# Sensors.net
KiCad netlist of a schematic drawn in Altium Designer
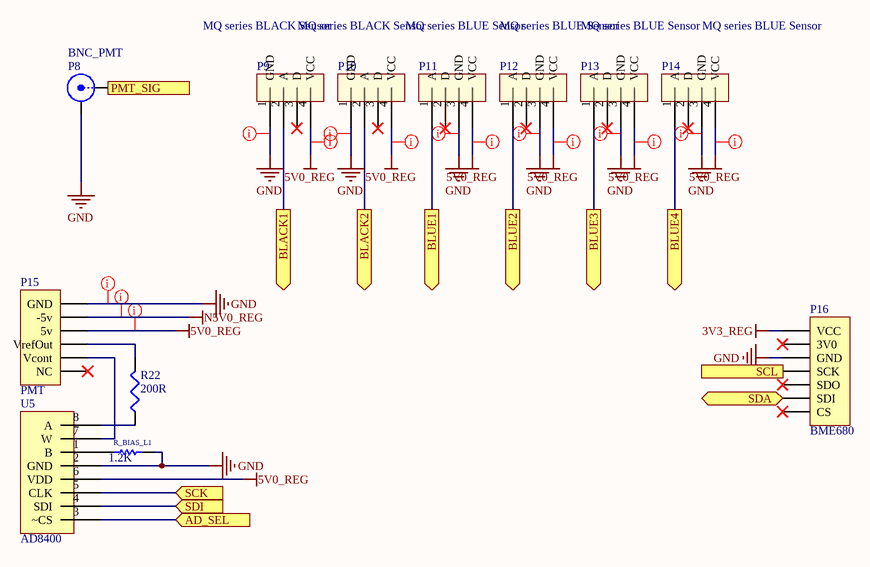
[diagram p0: Sensors.SchDoc]

(export (version "E")
  (design (tool "Eeschema 10.0.6"))
  (components
    (comp (ref "P8")
      (value "BNC_PMT")
      (footprint "BNC_RA CON")
      (description "BNC Elbow Connector")
      (fields (field (name "PUBLISHER") "Altium Limited"))
      (libsource (lib "Miscellaneous Connectors") (part "BNC"))
    )
    (comp (ref "P9")
      (value "MQ series BLACK Sensor")
      (footprint "MQ series BLACK sensor")
      (libsource (lib "ScienceComponents") (part "MQ series BLACK Sensor"))
    )
    (comp (ref "P10")
      (value "MQ series BLACK Sensor")
      (footprint "MQ series BLACK sensor")
      (libsource (lib "ScienceComponents") (part "MQ series BLACK Sensor"))
    )
    (comp (ref "P11")
      (value "MQ series BLUE Sensor")
      (footprint "MQ series BLUE sensor")
      (libsource (lib "ScienceComponents") (part "MQ series BLUE Sensor"))
    )
    (comp (ref "P12")
      (value "MQ series BLUE Sensor")
      (footprint "MQ series BLUE sensor")
      (libsource (lib "ScienceComponents") (part "MQ series BLUE Sensor"))
    )
    (comp (ref "P13")
      (value "MQ series BLUE Sensor")
      (footprint "MQ series BLUE sensor")
      (libsource (lib "ScienceComponents") (part "MQ series BLUE Sensor"))
    )
    (comp (ref "P14")
      (value "MQ series BLUE Sensor")
      (footprint "MQ series BLUE sensor")
      (libsource (lib "ScienceComponents") (part "MQ series BLUE Sensor"))
    )
    (comp (ref "P15")
      (value "PMT")
      (footprint "HDR1X6H")
      (description "Header, 6-Pin, Right Angle")
      (fields (field (name "PUBLISHER") "Altium Limited"))
      (libsource (lib "Miscellaneous Connectors") (part "Header 6H"))
    )
    (comp (ref "P16")
      (value "BME680")
      (footprint "HDR1X7")
      (description "Header, 7-Pin")
      (fields (field (name "PUBLISHER") "Altium Limited"))
      (libsource (lib "Miscellaneous Connectors") (part "Header 7"))
    )
    (comp (ref "R22")
      (value "200R")
      (footprint "RESC1608X06N_0603")
      (description "RES SMD 200 OHM 1% 1/4W 1206")
      (fields (field (name "TOLERANCE") "1%"))
      (libsource (lib "RSX_Resistors") (part "RC1206FR-07200RL"))
    )
    (comp (ref "R_BIAS_L1")
      (value "1.2K")
      (footprint "RESC1608X06N_0603")
      (description "Resistor")
      (fields (field (name "PUBLISHER") "Altium Limited"))
      (libsource (lib "Miscellaneous Devices") (part "Res1"))
    )
    (comp (ref "U5")
      (value "AD8400")
      (footprint "AD8400(SOIC8)")
      (libsource (lib "DUE") (part "Component_1"))
    )
  )
  (nets
    (net (code "1") (name "/AD_SEL") (class "Default")
      (node (ref "U5") (pin "3") (pinfunction "~CS_3") (pintype "passive"))
    )
    (net (code "2") (name "/BLACK1") (class "Default")
      (node (ref "P9") (pin "2") (pinfunction "A_2") (pintype "passive"))
    )
    (net (code "3") (name "/BLACK2") (class "Default")
      (node (ref "P10") (pin "2") (pinfunction "A_2") (pintype "passive"))
    )
    (net (code "4") (name "/BLUE1") (class "Default")
      (node (ref "P11") (pin "1") (pinfunction "A_1") (pintype "passive"))
    )
    (net (code "5") (name "/BLUE2") (class "Default")
      (node (ref "P12") (pin "1") (pinfunction "A_1") (pintype "passive"))
    )
    (net (code "6") (name "/BLUE3") (class "Default")
      (node (ref "P13") (pin "1") (pinfunction "A_1") (pintype "passive"))
    )
    (net (code "7") (name "/BLUE4") (class "Default")
      (node (ref "P14") (pin "1") (pinfunction "A_1") (pintype "passive"))
    )
    (net (code "8") (name "/PMT_SIG") (class "Default")
      (node (ref "P8") (pin "1") (pinfunction "X_1") (pintype "passive"))
    )
    (net (code "9") (name "/SCK") (class "Default")
      (node (ref "U5") (pin "5") (pinfunction "CLK_5") (pintype "passive"))
    )
    (net (code "10") (name "/SCL") (class "Default")
      (node (ref "P16") (pin "4") (pinfunction "SCK_4") (pintype "passive"))
    )
    (net (code "11") (name "/SDA") (class "Default")
      (node (ref "P16") (pin "6") (pinfunction "SDI_6") (pintype "passive"))
    )
    (net (code "12") (name "/SDI") (class "Default")
      (node (ref "U5") (pin "4") (pinfunction "SDI_4") (pintype "passive"))
    )
    (net (code "13") (name "3V3_REG") (class "Default")
      (node (ref "P16") (pin "1") (pinfunction "VCC_1") (pintype "passive"))
    )
    (net (code "14") (name "5V0_REG") (class "Default")
      (node (ref "P10") (pin "4") (pinfunction "VCC_4") (pintype "passive"))
      (node (ref "P11") (pin "4") (pinfunction "VCC_4") (pintype "passive"))
      (node (ref "P12") (pin "4") (pinfunction "VCC_4") (pintype "passive"))
      (node (ref "P13") (pin "4") (pinfunction "VCC_4") (pintype "passive"))
      (node (ref "P14") (pin "4") (pinfunction "VCC_4") (pintype "passive"))
      (node (ref "P15") (pin "6") (pinfunction "5v_6") (pintype "passive"))
      (node (ref "P9") (pin "4") (pinfunction "VCC_4") (pintype "passive"))
      (node (ref "U5") (pin "6") (pinfunction "VDD_6") (pintype "passive"))
    )
    (net (code "15") (name "GND") (class "Default")
      (node (ref "P10") (pin "1") (pinfunction "GND_1") (pintype "passive"))
      (node (ref "P11") (pin "3") (pinfunction "GND_3") (pintype "passive"))
      (node (ref "P12") (pin "3") (pinfunction "GND_3") (pintype "passive"))
      (node (ref "P13") (pin "3") (pinfunction "GND_3") (pintype "passive"))
      (node (ref "P14") (pin "3") (pinfunction "GND_3") (pintype "passive"))
      (node (ref "P15") (pin "4") (pinfunction "GND_4") (pintype "passive"))
      (node (ref "P16") (pin "3") (pinfunction "GND_3") (pintype "passive"))
      (node (ref "P8") (pin "2") (pinfunction "Y_2") (pintype "passive"))
      (node (ref "P9") (pin "1") (pinfunction "GND_1") (pintype "passive"))
      (node (ref "R_BIAS_L1") (pin "2") (pinfunction "2_2") (pintype "passive"))
      (node (ref "U5") (pin "2") (pinfunction "GND_2") (pintype "passive"))
    )
    (net (code "16") (name "N5V0_REG") (class "Default")
      (node (ref "P15") (pin "5") (pinfunction "-5v_5") (pintype "passive"))
    )
    (net (code "17") (name "Net-(P15-Vcont)") (class "Default")
      (node (ref "P15") (pin "2") (pinfunction "Vcont_2") (pintype "passive"))
      (node (ref "U5") (pin "7") (pinfunction "W_7") (pintype "passive"))
    )
    (net (code "18") (name "Net-(P15-VrefOut)") (class "Default")
      (node (ref "P15") (pin "3") (pinfunction "VrefOut_3") (pintype "passive"))
      (node (ref "R22") (pin "2") (pinfunction "2_2") (pintype "passive"))
    )
    (net (code "19") (name "Net-(U5-A)") (class "Default")
      (node (ref "R22") (pin "1") (pinfunction "1_1") (pintype "passive"))
      (node (ref "U5") (pin "8") (pinfunction "A_8") (pintype "passive"))
    )
    (net (code "20") (name "Net-(U5-B)") (class "Default")
      (node (ref "R_BIAS_L1") (pin "1") (pinfunction "1_1") (pintype "passive"))
      (node (ref "U5") (pin "1") (pinfunction "B_1") (pintype "passive"))
    )
    (net (code "21") (name "unconnected-(P9-D-Pad3)") (class "Default")
      (node (ref "P9") (pin "3") (pinfunction "D_3") (pintype "passive+no_connect"))
    )
    (net (code "22") (name "unconnected-(P10-D-Pad3)") (class "Default")
      (node (ref "P10") (pin "3") (pinfunction "D_3") (pintype "passive+no_connect"))
    )
    (net (code "23") (name "unconnected-(P11-D-Pad2)") (class "Default")
      (node (ref "P11") (pin "2") (pinfunction "D_2") (pintype "passive+no_connect"))
    )
    (net (code "24") (name "unconnected-(P12-D-Pad2)") (class "Default")
      (node (ref "P12") (pin "2") (pinfunction "D_2") (pintype "passive+no_connect"))
    )
    (net (code "25") (name "unconnected-(P13-D-Pad2)") (class "Default")
      (node (ref "P13") (pin "2") (pinfunction "D_2") (pintype "passive+no_connect"))
    )
    (net (code "26") (name "unconnected-(P14-D-Pad2)") (class "Default")
      (node (ref "P14") (pin "2") (pinfunction "D_2") (pintype "passive+no_connect"))
    )
    (net (code "27") (name "unconnected-(P15-NC-Pad1)") (class "Default")
      (node (ref "P15") (pin "1") (pinfunction "NC_1") (pintype "passive+no_connect"))
    )
    (net (code "28") (name "unconnected-(P16-3V0-Pad2)") (class "Default")
      (node (ref "P16") (pin "2") (pinfunction "3V0_2") (pintype "passive+no_connect"))
    )
    (net (code "29") (name "unconnected-(P16-CS-Pad7)") (class "Default")
      (node (ref "P16") (pin "7") (pinfunction "CS_7") (pintype "passive+no_connect"))
    )
    (net (code "30") (name "unconnected-(P16-SDO-Pad5)") (class "Default")
      (node (ref "P16") (pin "5") (pinfunction "SDO_5") (pintype "passive+no_connect"))
    )
  )
)
